# Audio_Module.net
KiCad netlist of a schematic drawn in Altium Designer
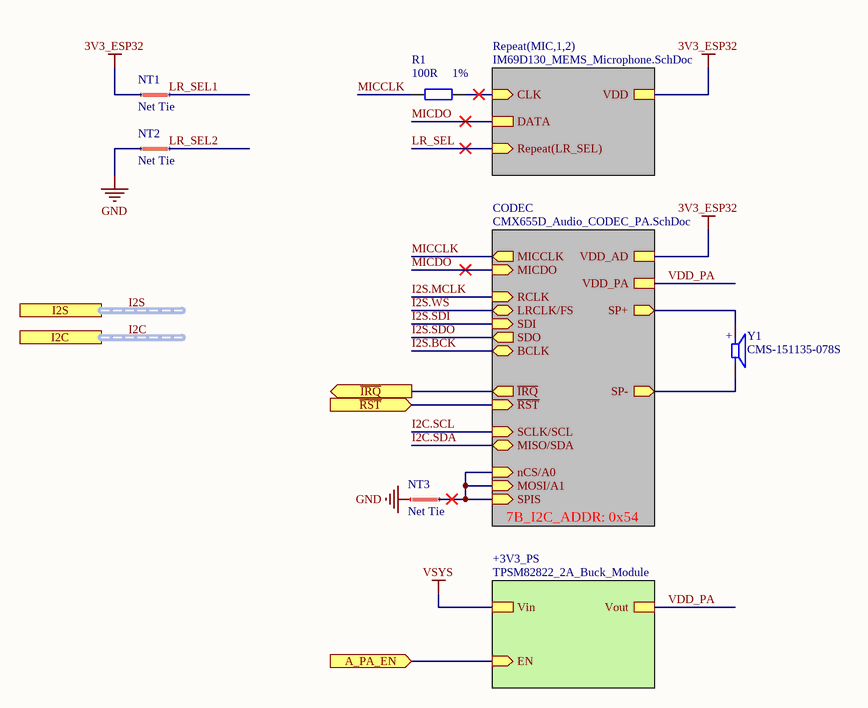
[diagram p0: Audio_Module.SchDoc]

(export (version "E")
  (design (tool "Eeschema 10.0.6"))
  (components
    (comp (ref "NT1")
      (value "Net Tie")
      (footprint "Net Tie 6x30mil")
      (libsource (lib "BLDC_Motor_Driver") (part "Net Tie Line"))
    )
    (comp (ref "NT2")
      (value "Net Tie")
      (footprint "Net Tie 6x30mil")
      (libsource (lib "BLDC_Motor_Driver") (part "Net Tie Line"))
    )
    (comp (ref "NT3")
      (value "Net Tie")
      (footprint "Net Tie 6x30mil")
      (libsource (lib "BLDC_Motor_Driver") (part "Net Tie Line"))
    )
    (comp (ref "R1")
      (value "RES SMD 100 OHM 1% 1/16W 0402")
      (footprint "0402R")
      (description "100 Ohms ±1% 0.063W, 1/16W Chip Resistor 0402 (1005 Metric) Moisture Resistant Thick Film")
      (fields
        (field (name "MANUFACTURER") "Yageo")
        (field (name "MANUFACTURER PART NUMBER") "RC0402FR-07100RL")
        (field (name "TOLERANCE") "1%")
        (field (name "RESISTANCE") "100R")
      )
      (libsource (lib "resistors_smd") (part "RES SMD 100 OHM 1% 1/16W 0402"))
    )
    (comp (ref "Y1")
      (value "CMS-151135-078S")
      (footprint "SPKR_CMS-151135-078S")
      (description "8 Ohms General Purpose Speaker 700mW 100Hz ~ 20kHz Top Rectangular")
      (fields (field (name "MANUFACTURER") "CUI"))
      (libsource (lib "BLDC_Motor_Driver") (part "SPEAKER CMS-151135-078S 15 X 11 MM ENCLOSED"))
    )
  )
  (nets
    (net (code "4") (name "/CLK") (class "Default")
      (node (ref "R1") (pin "1") (pinfunction "1_1") (pintype "passive"))
    )
    (net (code "14") (name "/LR_SEL1") (class "Default") (node (ref "NT1") (pin "2") (pintype "passive")))
    (net (code "15") (name "/LR_SEL2") (class "Default") (node (ref "NT2") (pin "2") (pintype "passive")))
    (net (code "16") (name "/MICCLK") (class "Default")
      (node (ref "R1") (pin "2") (pinfunction "2_2") (pintype "passive"))
    )
    (net (code "18") (name "/MOSI{slash}A1") (class "Default")
      (node (ref "NT3") (pin "2") (pintype "passive"))
    )
    (net (code "20") (name "/SP+") (class "Default")
      (node (ref "Y1") (pin "P") (pinfunction "1_P") (pintype "passive"))
    )
    (net (code "21") (name "/SP-") (class "Default")
      (node (ref "Y1") (pin "M") (pinfunction "2_M") (pintype "passive"))
    )
    (net (code "25") (name "3V3_ESP32") (class "Default") (node (ref "NT1") (pin "1") (pintype "passive")))
    (net (code "26") (name "GND") (class "Default")
      (node (ref "NT2") (pin "1") (pintype "passive"))
      (node (ref "NT3") (pin "1") (pintype "passive"))
    )
  )
)
